# Transformer.net
KiCad netlist of a schematic drawn in Altium Designer
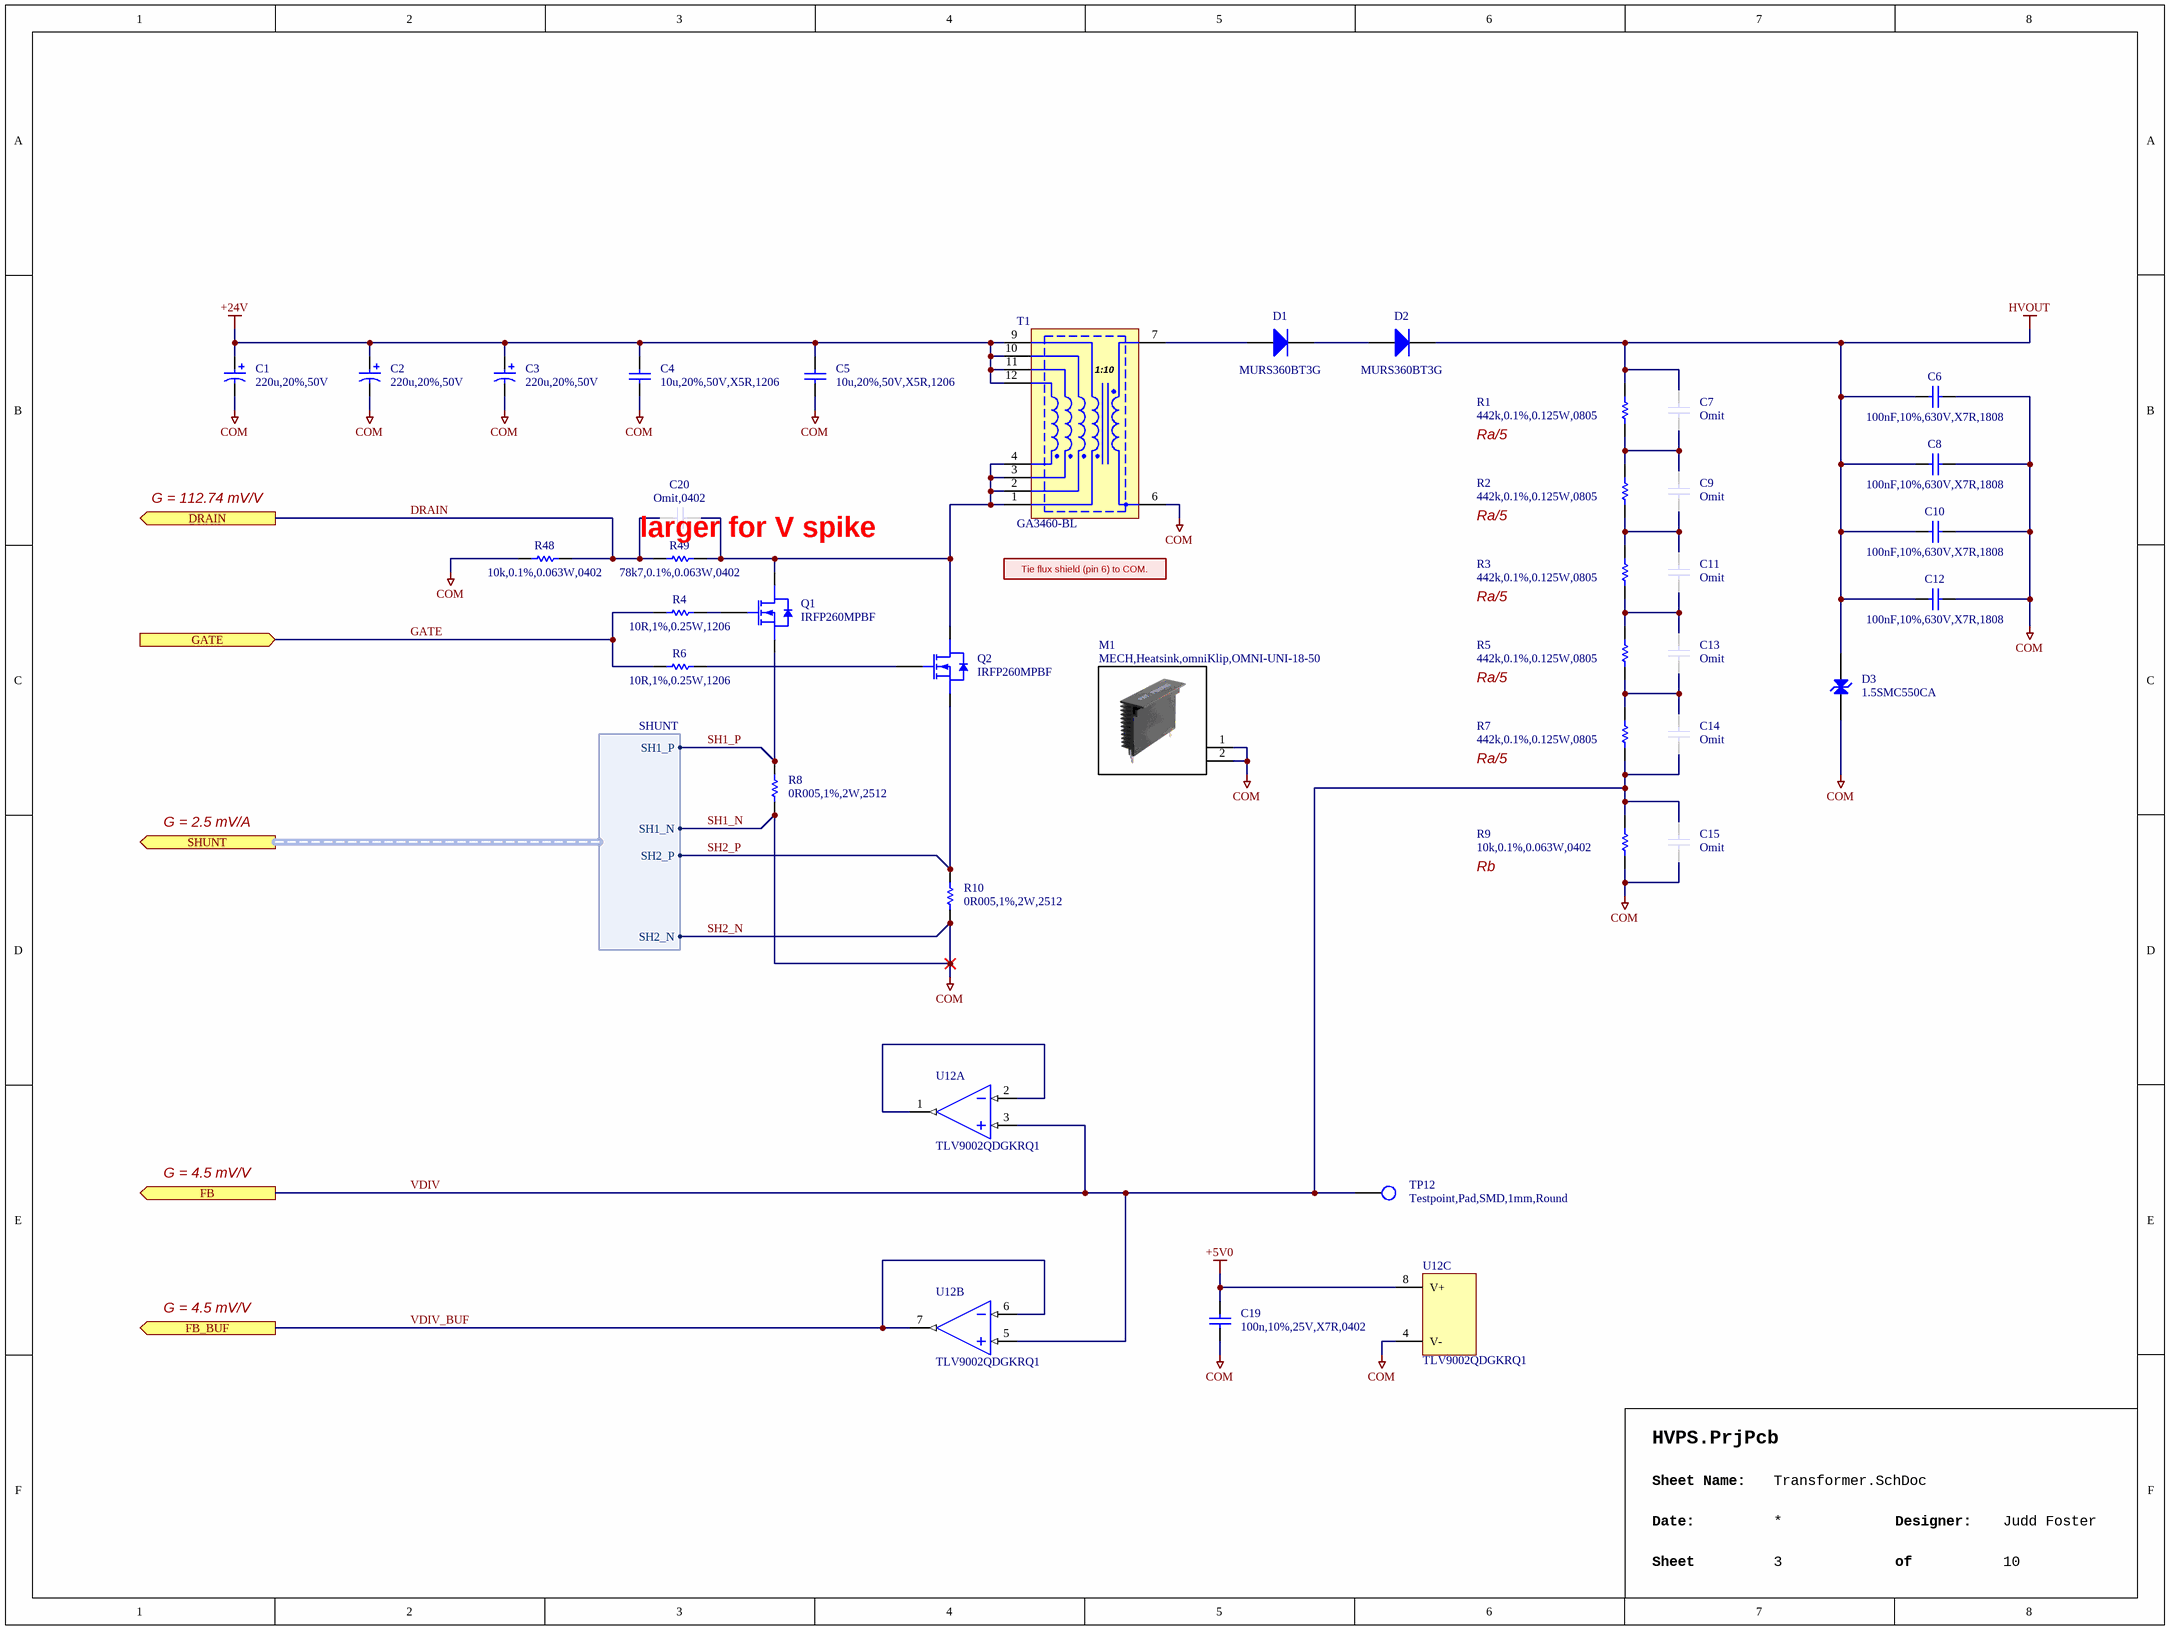
[diagram p0: Transformer.SchDoc]

(export (version "E")
  (design (tool "Eeschema 10.0.6"))
  (components
    (comp (ref "C1")
      (value "220u,20%,50V")
      (footprint "CAPPR500W60D1000H1600B")
      (description "220 ï¿½F 50 V Aluminum Electrolytic Capacitors Radial, Can 5000 Hrs @ 105ï¿½C")
      (fields
        (field (name "MANUFACTURER 1 PART NUMBER") "50YXG220MEFCT810X16")
        (field (name "VENDOR 1 PART NUMBER") "1189-3771-1-ND")
        (field (name "CREATEDBY") "Judd Foster")
      )
      (libsource (lib "Component Library") (part "CAP,Alum,220uF,20%,50VDC,Radial,Thru"))
    )
    (comp (ref "C2")
      (value "220u,20%,50V")
      (footprint "CAPPR500W60D1000H1600B")
      (description "220 ï¿½F 50 V Aluminum Electrolytic Capacitors Radial, Can 5000 Hrs @ 105ï¿½C")
      (fields
        (field (name "MANUFACTURER 1 PART NUMBER") "50YXG220MEFCT810X16")
        (field (name "VENDOR 1 PART NUMBER") "1189-3771-1-ND")
        (field (name "CREATEDBY") "Judd Foster")
      )
      (libsource (lib "Component Library") (part "CAP,Alum,220uF,20%,50VDC,Radial,Thru"))
    )
    (comp (ref "C3")
      (value "220u,20%,50V")
      (footprint "CAPPR500W60D1000H1600B")
      (description "220 ï¿½F 50 V Aluminum Electrolytic Capacitors Radial, Can 5000 Hrs @ 105ï¿½C")
      (fields
        (field (name "MANUFACTURER 1 PART NUMBER") "50YXG220MEFCT810X16")
        (field (name "VENDOR 1 PART NUMBER") "1189-3771-1-ND")
        (field (name "CREATEDBY") "Judd Foster")
      )
      (libsource (lib "Component Library") (part "CAP,Alum,220uF,20%,50VDC,Radial,Thru"))
    )
    (comp (ref "C4")
      (value "10u,20%,50V,X5R,1206")
      (footprint "CAPC3216X16N")
      (description "10ï¿½F ï¿½20% 50V Ceramic Capacitor X5R 1206 (3216 Metric)")
      (fields
        (field (name "MANUFACTURER 1 PART NUMBER") "CL31A106MBHNNNE")
        (field (name "VENDOR 1 PART NUMBER") "1276-6736-1-ND")
        (field (name "CREATEDBY") "Judd Foster")
      )
      (libsource (lib "Component Library") (part "CAP,Cer,10uF,50VDC,X5R,1206"))
    )
    (comp (ref "C5")
      (value "10u,20%,50V,X5R,1206")
      (footprint "CAPC3216X16N")
      (description "10ï¿½F ï¿½20% 50V Ceramic Capacitor X5R 1206 (3216 Metric)")
      (fields
        (field (name "MANUFACTURER 1 PART NUMBER") "CL31A106MBHNNNE")
        (field (name "VENDOR 1 PART NUMBER") "1276-6736-1-ND")
        (field (name "CREATEDBY") "Judd Foster")
      )
      (libsource (lib "Component Library") (part "CAP,Cer,10uF,50VDC,X5R,1206"))
    )
    (comp (ref "C6")
      (value "100nF,10%,630V,X7R,1808")
      (footprint "KEMET_PKG_LC")
      (description "0.1 ÂµF Â±10% 630V Ceramic Capacitor X7R 1808 (4520 Metric)")
      (fields
        (field (name "MANUFACTURER 1 PART NUMBER") "C1808C104KBRAC7800")
        (field (name "VENDOR 1 PART NUMBER") "399-C1808C104KBRAC7800CT-ND")
        (field (name "CREATEDBY") "Judd Foster")
      )
      (libsource (lib "Component Library") (part "CAP,Cer,100nF,10%,630V,X7R,1808"))
    )
    (comp (ref "C7")
      (value "Omit")
      (footprint "CAPC_0805")
      (fields (field (name "CREATEDBY") "Judd Foster"))
      (libsource (lib "Component Library") (part "CAP,Omit,0805"))
    )
    (comp (ref "C8")
      (value "100nF,10%,630V,X7R,1808")
      (footprint "KEMET_PKG_LC")
      (description "0.1 ÂµF Â±10% 630V Ceramic Capacitor X7R 1808 (4520 Metric)")
      (fields
        (field (name "MANUFACTURER 1 PART NUMBER") "C1808C104KBRAC7800")
        (field (name "VENDOR 1 PART NUMBER") "399-C1808C104KBRAC7800CT-ND")
        (field (name "CREATEDBY") "Judd Foster")
      )
      (libsource (lib "Component Library") (part "CAP,Cer,100nF,10%,630V,X7R,1808"))
    )
    (comp (ref "C9")
      (value "Omit")
      (footprint "CAPC_0805")
      (fields (field (name "CREATEDBY") "Judd Foster"))
      (libsource (lib "Component Library") (part "CAP,Omit,0805"))
    )
    (comp (ref "C10")
      (value "100nF,10%,630V,X7R,1808")
      (footprint "KEMET_PKG_LC")
      (description "0.1 ÂµF Â±10% 630V Ceramic Capacitor X7R 1808 (4520 Metric)")
      (fields
        (field (name "MANUFACTURER 1 PART NUMBER") "C1808C104KBRAC7800")
        (field (name "VENDOR 1 PART NUMBER") "399-C1808C104KBRAC7800CT-ND")
        (field (name "CREATEDBY") "Judd Foster")
      )
      (libsource (lib "Component Library") (part "CAP,Cer,100nF,10%,630V,X7R,1808"))
    )
    (comp (ref "C11")
      (value "Omit")
      (footprint "CAPC_0805")
      (fields (field (name "CREATEDBY") "Judd Foster"))
      (libsource (lib "Component Library") (part "CAP,Omit,0805"))
    )
    (comp (ref "C12")
      (value "100nF,10%,630V,X7R,1808")
      (footprint "KEMET_PKG_LC")
      (description "0.1 ÂµF Â±10% 630V Ceramic Capacitor X7R 1808 (4520 Metric)")
      (fields
        (field (name "MANUFACTURER 1 PART NUMBER") "C1808C104KBRAC7800")
        (field (name "VENDOR 1 PART NUMBER") "399-C1808C104KBRAC7800CT-ND")
        (field (name "CREATEDBY") "Judd Foster")
      )
      (libsource (lib "Component Library") (part "CAP,Cer,100nF,10%,630V,X7R,1808"))
    )
    (comp (ref "C13")
      (value "Omit")
      (footprint "CAPC_0805")
      (fields (field (name "CREATEDBY") "Judd Foster"))
      (libsource (lib "Component Library") (part "CAP,Omit,0805"))
    )
    (comp (ref "C14")
      (value "Omit")
      (footprint "CAPC_0805")
      (fields (field (name "CREATEDBY") "Judd Foster"))
      (libsource (lib "Component Library") (part "CAP,Omit,0805"))
    )
    (comp (ref "C15")
      (value "Omit")
      (footprint "CAPC_0805")
      (fields (field (name "CREATEDBY") "Judd Foster"))
      (libsource (lib "Component Library") (part "CAP,Omit,0805"))
    )
    (comp (ref "C19")
      (value "100n,10%,25V,X7R,0402")
      (footprint "CAPC1005X06N")
      (description "0.1ï¿½F ï¿½10% 25V Ceramic Capacitor X7R 0402 (1005 Metric)")
      (fields
        (field (name "MANUFACTURER 1 PART NUMBER") "GRM155R71E104KE14J")
        (field (name "VENDOR 1 PART NUMBER") "490-14603-1-ND")
        (field (name "CREATEDBY") "Judd Foster")
      )
      (libsource (lib "Component Library") (part "CAP,Cer,100nF,10%,25V,X7R,0402"))
    )
    (comp (ref "C20")
      (value "Omit,0402")
      (footprint "CAPC1005X06N")
      (description "Omit")
      (fields (field (name "CREATEDBY") "Judd Foster"))
      (libsource (lib "Component Library") (part "CAP,Omit,0402"))
    )
    (comp (ref "D1")
      (value "MURS360BT3G")
      (footprint "ONSEMI_SMB")
      (description "Diode 600 V 3A Surface Mount SMB")
      (fields
        (field (name "VENDOR 1 PART NUMBER") "MURS360BT3GOSCT-ND")
        (field (name "CREATEDBY") "Judd Foster")
      )
      (libsource (lib "Component Library") (part "DIODE,Gen,600V,3A,SMB"))
    )
    (comp (ref "D2")
      (value "MURS360BT3G")
      (footprint "ONSEMI_SMB")
      (description "Diode 600 V 3A Surface Mount SMB")
      (fields
        (field (name "VENDOR 1 PART NUMBER") "MURS360BT3GOSCT-ND")
        (field (name "CREATEDBY") "Judd Foster")
      )
      (libsource (lib "Component Library") (part "DIODE,Gen,600V,3A,SMB"))
    )
    (comp (ref "D3")
      (value "1.5SMC550CA")
      (footprint "LITTELFUSE_DO-214AB")
      (description "760V Clamp 2A Ipp Tvs Diode Surface Mount DO-214AB (SMCJ)")
      (fields
        (field (name "VENDOR 1 PART NUMBER") "1.5SMC550CACT-ND")
        (field (name "CREATEDBY") "Judd Foster")
      )
      (libsource (lib "Component Library") (part "DIODE,TVS,495VWM,SMD"))
    )
    (comp (ref "M1")
      (value "MECH,Heatsink,omniKlip,OMNI-UNI-18-50")
      (footprint "WAKEFIELD_OMNI-UNI-18-50")
      (description "Heat Sinks omniKlip Heat Sink for TO-247, TO-264, 18mm Wide, 50mm Long, Aluminum")
      (fields
        (field (name "MANUFACTURER 1 PART NUMBER") "OMNI-UNI-18-50")
        (field (name "VENDOR 1 PART NUMBER") "567-OMNI-UNI-18-50")
        (field (name "CREATEDBY") "Judd Foster")
      )
      (libsource (lib "Component Library") (part "MECH,Heatsink,omniKlip,OMNI-UNI-18-50"))
    )
    (comp (ref "Q1")
      (value "IRFP260MPBF")
      (footprint "INFINEON_PKG_TO247AD")
      (description "N-Channel 200 V 50A (Tc) 300W (Tc) Through Hole TO-247AC")
      (fields (field (name "VENDOR 1 PART NUMBER") "IRFP260MPBF-ND") (field (name "CREATEDBY") "Judd Foster"))
      (libsource (lib "Component Library") (part "MOSFET,N Ch,200V,50A,IRFP260MPBF"))
    )
    (comp (ref "Q2")
      (value "IRFP260MPBF")
      (footprint "INFINEON_PKG_TO247AD")
      (description "N-Channel 200 V 50A (Tc) 300W (Tc) Through Hole TO-247AC")
      (fields (field (name "VENDOR 1 PART NUMBER") "IRFP260MPBF-ND") (field (name "CREATEDBY") "Judd Foster"))
      (libsource (lib "Component Library") (part "MOSFET,N Ch,200V,50A,IRFP260MPBF"))
    )
    (comp (ref "R1")
      (value "442k,0.1%,0.125W,0805")
      (footprint "RESC2012X07N")
      (description "442 kOhms Â±0.1% 0.125W, 1/8W Chip Resistor 0805 (2012 Metric) Automotive AEC-Q200 Thin Film")
      (fields
        (field (name "MANUFACTURER 1 PART NUMBER") "ERA-6AEB4423V")
        (field (name "VENDOR 1 PART NUMBER") "P442KDACT-ND")
        (field (name "CREATEDBY") "Judd Foster")
      )
      (libsource (lib "Component Library") (part "RES,442k,0.1%,0.125W,0805"))
    )
    (comp (ref "R2")
      (value "442k,0.1%,0.125W,0805")
      (footprint "RESC2012X07N")
      (description "442 kOhms Â±0.1% 0.125W, 1/8W Chip Resistor 0805 (2012 Metric) Automotive AEC-Q200 Thin Film")
      (fields
        (field (name "MANUFACTURER 1 PART NUMBER") "ERA-6AEB4423V")
        (field (name "VENDOR 1 PART NUMBER") "P442KDACT-ND")
        (field (name "CREATEDBY") "Judd Foster")
      )
      (libsource (lib "Component Library") (part "RES,442k,0.1%,0.125W,0805"))
    )
    (comp (ref "R3")
      (value "442k,0.1%,0.125W,0805")
      (footprint "RESC2012X07N")
      (description "442 kOhms Â±0.1% 0.125W, 1/8W Chip Resistor 0805 (2012 Metric) Automotive AEC-Q200 Thin Film")
      (fields
        (field (name "MANUFACTURER 1 PART NUMBER") "ERA-6AEB4423V")
        (field (name "VENDOR 1 PART NUMBER") "P442KDACT-ND")
        (field (name "CREATEDBY") "Judd Foster")
      )
      (libsource (lib "Component Library") (part "RES,442k,0.1%,0.125W,0805"))
    )
    (comp (ref "R4")
      (value "10R,1%,0.25W,1206")
      (footprint "RESC3216X06N")
      (fields
        (field (name "MANUFACTURER 1 PART NUMBER") "CRGCQ1206F10R")
        (field (name "VENDOR 1 PART NUMBER") "A129786CT-ND")
        (field (name "CREATEDBY") "Judd Foster")
      )
      (libsource (lib "Component Library") (part "RES,10R,1%,0.25W,1206"))
    )
    (comp (ref "R5")
      (value "442k,0.1%,0.125W,0805")
      (footprint "RESC2012X07N")
      (description "442 kOhms Â±0.1% 0.125W, 1/8W Chip Resistor 0805 (2012 Metric) Automotive AEC-Q200 Thin Film")
      (fields
        (field (name "MANUFACTURER 1 PART NUMBER") "ERA-6AEB4423V")
        (field (name "VENDOR 1 PART NUMBER") "P442KDACT-ND")
        (field (name "CREATEDBY") "Judd Foster")
      )
      (libsource (lib "Component Library") (part "RES,442k,0.1%,0.125W,0805"))
    )
    (comp (ref "R6")
      (value "10R,1%,0.25W,1206")
      (footprint "RESC3216X06N")
      (fields
        (field (name "MANUFACTURER 1 PART NUMBER") "CRGCQ1206F10R")
        (field (name "VENDOR 1 PART NUMBER") "A129786CT-ND")
        (field (name "CREATEDBY") "Judd Foster")
      )
      (libsource (lib "Component Library") (part "RES,10R,1%,0.25W,1206"))
    )
    (comp (ref "R7")
      (value "442k,0.1%,0.125W,0805")
      (footprint "RESC2012X07N")
      (description "442 kOhms Â±0.1% 0.125W, 1/8W Chip Resistor 0805 (2012 Metric) Automotive AEC-Q200 Thin Film")
      (fields
        (field (name "MANUFACTURER 1 PART NUMBER") "ERA-6AEB4423V")
        (field (name "VENDOR 1 PART NUMBER") "P442KDACT-ND")
        (field (name "CREATEDBY") "Judd Foster")
      )
      (libsource (lib "Component Library") (part "RES,442k,0.1%,0.125W,0805"))
    )
    (comp (ref "R8")
      (value "0R005,1%,2W,2512")
      (footprint "OHMITE_PKG_MCS3264")
      (fields
        (field (name "MANUFACTURER 1 PART NUMBER") "MCS3264R005FER")
        (field (name "VENDOR 1 PART NUMBER") "MCS3264R005FERCT-ND")
        (field (name "CREATEDBY") "Judd Foster")
      )
      (libsource (lib "Component Library") (part "RES,0R005,1%,2W,2512"))
    )
    (comp (ref "R9")
      (value "10k,0.1%,0.063W,0402")
      (footprint "RESC1005X04N")
      (description "10 kOhms ï¿½0.1% 0.1W, 1/10W Chip Resistor 0402 (1005 Metric) Automotive AEC-Q200 Thin Film")
      (fields
        (field (name "MANUFACTURER 1 PART NUMBER") "RNCF0402BTE10K0")
        (field (name "VENDOR 1 PART NUMBER") "RNCF0402BTE10K0CT-ND")
        (field (name "CREATEDBY") "Judd Foster")
      )
      (libsource (lib "Component Library") (part "RES,10k,0.1%,0.063W,0402"))
    )
    (comp (ref "R10")
      (value "0R005,1%,2W,2512")
      (footprint "OHMITE_PKG_MCS3264")
      (fields
        (field (name "MANUFACTURER 1 PART NUMBER") "MCS3264R005FER")
        (field (name "VENDOR 1 PART NUMBER") "MCS3264R005FERCT-ND")
        (field (name "CREATEDBY") "Judd Foster")
      )
      (libsource (lib "Component Library") (part "RES,0R005,1%,2W,2512"))
    )
    (comp (ref "R48")
      (value "10k,0.1%,0.063W,0402")
      (footprint "RESC1005X04N")
      (description "10 kOhms ï¿½0.1% 0.1W, 1/10W Chip Resistor 0402 (1005 Metric) Automotive AEC-Q200 Thin Film")
      (fields
        (field (name "MANUFACTURER 1 PART NUMBER") "RNCF0402BTE10K0")
        (field (name "VENDOR 1 PART NUMBER") "RNCF0402BTE10K0CT-ND")
        (field (name "CREATEDBY") "Judd Foster")
      )
      (libsource (lib "Component Library") (part "RES,10k,0.1%,0.063W,0402"))
    )
    (comp (ref "R49")
      (value "78k7,0.1%,0.063W,0402")
      (footprint "RESC1005X04N")
      (description "78.7 kOhms ï¿½0.1% 0.063W, 1/16W Chip Resistor 0402 (1005 Metric) Thin Film")
      (fields
        (field (name "MANUFACTURER 1 PART NUMBER") "RT0402BRD0778K7L")
        (field (name "VENDOR 1 PART NUMBER") "YAG4311CT-ND")
        (field (name "CREATEDBY") "Judd Foster")
      )
      (libsource (lib "Component Library") (part "RES,78k7,0.1%,0.063W,0402"))
    )
    (comp (ref "T1")
      (value "GA3460-BL")
      (footprint "COILCRAFT_GA3460-BL")
      (description "Audio Transformers / Signal Transformers GA3460 for LT3751 500V 50A")
      (fields (field (name "VENDOR 1 PART NUMBER") "994-GA3460-BL") (field (name "CREATEDBY") "Judd Foster"))
      (libsource (lib "Component Library") (part "XFR,Flyback,COILCRAFT_GA3460-BL"))
    )
    (comp (ref "TP12")
      (value "Testpoint,Pad,SMD,1mm,Round")
      (footprint "TP100")
      (description "PCB Testpoint 1mm Round")
      (fields (field (name "CREATEDBY") "Judd Foster"))
      (libsource (lib "Component Library") (part "Testpoint,Pad,SMD"))
    )
    (comp (ref "U12")
      (value "TLV9002QDGKRQ1")
      (footprint "SOP65P490X110-8")
      (description "General Purpose Amplifier Circuit Rail-to-Rail 8-VSSOP")
      (fields
        (field (name "VENDOR 1 PART NUMBER") "296-TLV9002QDGKRQ1CT-ND")
        (field (name "CREATEDBY") "Judd Foster")
      )
      (libsource (lib "") (part "TLV9002QDGKRQ1_1"))
    )
  )
  (nets
    (net (code "2") (name "+5V0") (class "Default")
      (node (ref "C19") (pin "2") (pinfunction "2_2") (pintype "passive"))
      (node (ref "U12") (pin "8") (pinfunction "V+_8") (pintype "power_in"))
    )
    (net (code "3") (name "+24V") (class "Default")
      (node (ref "C1") (pin "1") (pinfunction "1_1") (pintype "passive"))
      (node (ref "C2") (pin "1") (pinfunction "1_1") (pintype "passive"))
      (node (ref "C3") (pin "1") (pinfunction "1_1") (pintype "passive"))
      (node (ref "C4") (pin "2") (pinfunction "2_2") (pintype "passive"))
      (node (ref "C5") (pin "2") (pinfunction "2_2") (pintype "passive"))
      (node (ref "T1") (pin "10") (pinfunction "10_10") (pintype "passive"))
      (node (ref "T1") (pin "11") (pinfunction "11_11") (pintype "passive"))
      (node (ref "T1") (pin "12") (pinfunction "12_12") (pintype "passive"))
      (node (ref "T1") (pin "9") (pinfunction "9_9") (pintype "passive"))
    )
    (net (code "4") (name "/DRAIN") (class "Default")
      (node (ref "C20") (pin "1") (pinfunction "1_1") (pintype "passive"))
      (node (ref "R48") (pin "1") (pinfunction "1_1") (pintype "passive"))
      (node (ref "R49") (pin "1") (pinfunction "1_1") (pintype "passive"))
    )
    (net (code "5") (name "/GATE") (class "Default")
      (node (ref "R4") (pin "1") (pinfunction "1_1") (pintype "passive"))
      (node (ref "R6") (pin "1") (pinfunction "1_1") (pintype "passive"))
    )
    (net (code "6") (name "/SH1_P") (class "Default")
      (node (ref "Q1") (pin "3") (pinfunction "S_3") (pintype "passive"))
      (node (ref "R8") (pin "2") (pinfunction "2_2") (pintype "passive"))
    )
    (net (code "7") (name "/SH2_P") (class "Default")
      (node (ref "Q2") (pin "3") (pinfunction "S_3") (pintype "passive"))
      (node (ref "R10") (pin "2") (pinfunction "2_2") (pintype "passive"))
    )
    (net (code "8") (name "/VDIV") (class "Default")
      (node (ref "C14") (pin "1") (pinfunction "1_1") (pintype "passive"))
      (node (ref "C15") (pin "2") (pinfunction "2_2") (pintype "passive"))
      (node (ref "R7") (pin "1") (pinfunction "1_1") (pintype "passive"))
      (node (ref "R9") (pin "2") (pinfunction "2_2") (pintype "passive"))
      (node (ref "TP12") (pin "1") (pinfunction "TP_1") (pintype "passive"))
      (node (ref "U12") (pin "3") (pinfunction "IN1+_3") (pintype "input"))
      (node (ref "U12") (pin "5") (pinfunction "IN2+_5") (pintype "input"))
    )
    (net (code "9") (name "/VDIV_BUF") (class "Default")
      (node (ref "U12") (pin "6") (pinfunction "IN2-_6") (pintype "input"))
      (node (ref "U12") (pin "7") (pinfunction "OUT2_7") (pintype "output"))
    )
    (net (code "11") (name "COM") (class "Default")
      (node (ref "C1") (pin "2") (pinfunction "2_2") (pintype "passive"))
      (node (ref "C10") (pin "1") (pinfunction "1_1") (pintype "passive"))
      (node (ref "C12") (pin "1") (pinfunction "1_1") (pintype "passive"))
      (node (ref "C15") (pin "1") (pinfunction "1_1") (pintype "passive"))
      (node (ref "C19") (pin "1") (pinfunction "1_1") (pintype "passive"))
      (node (ref "C2") (pin "2") (pinfunction "2_2") (pintype "passive"))
      (node (ref "C3") (pin "2") (pinfunction "2_2") (pintype "passive"))
      (node (ref "C4") (pin "1") (pinfunction "1_1") (pintype "passive"))
      (node (ref "C5") (pin "1") (pinfunction "1_1") (pintype "passive"))
      (node (ref "C6") (pin "1") (pinfunction "1_1") (pintype "passive"))
      (node (ref "C8") (pin "1") (pinfunction "1_1") (pintype "passive"))
      (node (ref "D3") (pin "2") (pinfunction "A_2") (pintype "passive"))
      (node (ref "M1") (pin "1") (pinfunction "1_1") (pintype "passive"))
      (node (ref "M1") (pin "2") (pinfunction "2_2") (pintype "passive"))
      (node (ref "R10") (pin "1") (pinfunction "1_1") (pintype "passive"))
      (node (ref "R48") (pin "2") (pinfunction "2_2") (pintype "passive"))
      (node (ref "R8") (pin "1") (pinfunction "1_1") (pintype "passive"))
      (node (ref "R9") (pin "1") (pinfunction "1_1") (pintype "passive"))
      (node (ref "T1") (pin "6") (pinfunction "6_6") (pintype "passive"))
      (node (ref "U12") (pin "4") (pinfunction "V-_4") (pintype "power_in"))
    )
    (net (code "12") (name "HVOUT") (class "Default")
      (node (ref "C10") (pin "2") (pinfunction "2_2") (pintype "passive"))
      (node (ref "C12") (pin "2") (pinfunction "2_2") (pintype "passive"))
      (node (ref "C6") (pin "2") (pinfunction "2_2") (pintype "passive"))
      (node (ref "C7") (pin "2") (pinfunction "2_2") (pintype "passive"))
      (node (ref "C8") (pin "2") (pinfunction "2_2") (pintype "passive"))
      (node (ref "D2") (pin "1") (pinfunction "K_1") (pintype "passive"))
      (node (ref "D3") (pin "1") (pinfunction "K_1") (pintype "passive"))
      (node (ref "R1") (pin "2") (pinfunction "2_2") (pintype "passive"))
    )
    (net (code "13") (name "Net-(C7-Pad1)") (class "Default")
      (node (ref "C7") (pin "1") (pinfunction "1_1") (pintype "passive"))
      (node (ref "C9") (pin "2") (pinfunction "2_2") (pintype "passive"))
      (node (ref "R1") (pin "1") (pinfunction "1_1") (pintype "passive"))
      (node (ref "R2") (pin "2") (pinfunction "2_2") (pintype "passive"))
    )
    (net (code "14") (name "Net-(C11-Pad1)") (class "Default")
      (node (ref "C11") (pin "1") (pinfunction "1_1") (pintype "passive"))
      (node (ref "C13") (pin "2") (pinfunction "2_2") (pintype "passive"))
      (node (ref "R3") (pin "1") (pinfunction "1_1") (pintype "passive"))
      (node (ref "R5") (pin "2") (pinfunction "2_2") (pintype "passive"))
    )
    (net (code "15") (name "Net-(C11-Pad2)") (class "Default")
      (node (ref "C11") (pin "2") (pinfunction "2_2") (pintype "passive"))
      (node (ref "C9") (pin "1") (pinfunction "1_1") (pintype "passive"))
      (node (ref "R2") (pin "1") (pinfunction "1_1") (pintype "passive"))
      (node (ref "R3") (pin "2") (pinfunction "2_2") (pintype "passive"))
    )
    (net (code "16") (name "Net-(C13-Pad1)") (class "Default")
      (node (ref "C13") (pin "1") (pinfunction "1_1") (pintype "passive"))
      (node (ref "C14") (pin "2") (pinfunction "2_2") (pintype "passive"))
      (node (ref "R5") (pin "1") (pinfunction "1_1") (pintype "passive"))
      (node (ref "R7") (pin "2") (pinfunction "2_2") (pintype "passive"))
    )
    (net (code "17") (name "Net-(D1-A)") (class "Default")
      (node (ref "D1") (pin "2") (pinfunction "A_2") (pintype "passive"))
      (node (ref "T1") (pin "7") (pinfunction "7_7") (pintype "passive"))
    )
    (net (code "18") (name "Net-(D1-K)") (class "Default")
      (node (ref "D1") (pin "1") (pinfunction "K_1") (pintype "passive"))
      (node (ref "D2") (pin "2") (pinfunction "A_2") (pintype "passive"))
    )
    (net (code "19") (name "Net-(Q1-D)") (class "Default")
      (node (ref "C20") (pin "2") (pinfunction "2_2") (pintype "passive"))
      (node (ref "Q1") (pin "2") (pinfunction "D_2") (pintype "passive"))
      (node (ref "Q2") (pin "2") (pinfunction "D_2") (pintype "passive"))
      (node (ref "R49") (pin "2") (pinfunction "2_2") (pintype "passive"))
      (node (ref "T1") (pin "1") (pinfunction "1_1") (pintype "passive"))
      (node (ref "T1") (pin "2") (pinfunction "2_2") (pintype "passive"))
      (node (ref "T1") (pin "3") (pinfunction "3_3") (pintype "passive"))
      (node (ref "T1") (pin "4") (pinfunction "4_4") (pintype "passive"))
    )
    (net (code "20") (name "Net-(Q1-G)") (class "Default")
      (node (ref "Q1") (pin "1") (pinfunction "G_1") (pintype "passive"))
      (node (ref "R4") (pin "2") (pinfunction "2_2") (pintype "passive"))
    )
    (net (code "21") (name "Net-(Q2-G)") (class "Default")
      (node (ref "Q2") (pin "1") (pinfunction "G_1") (pintype "passive"))
      (node (ref "R6") (pin "2") (pinfunction "2_2") (pintype "passive"))
    )
    (net (code "22") (name "Net-(U12A-IN1-)") (class "Default")
      (node (ref "U12") (pin "1") (pinfunction "OUT1_1") (pintype "output"))
      (node (ref "U12") (pin "2") (pinfunction "IN1-_2") (pintype "input"))
    )
  )
)
